# projeto_jcarlos_compacta_C_pia_em_confli.net
KiCad netlist of a schematic drawn in EAGLE
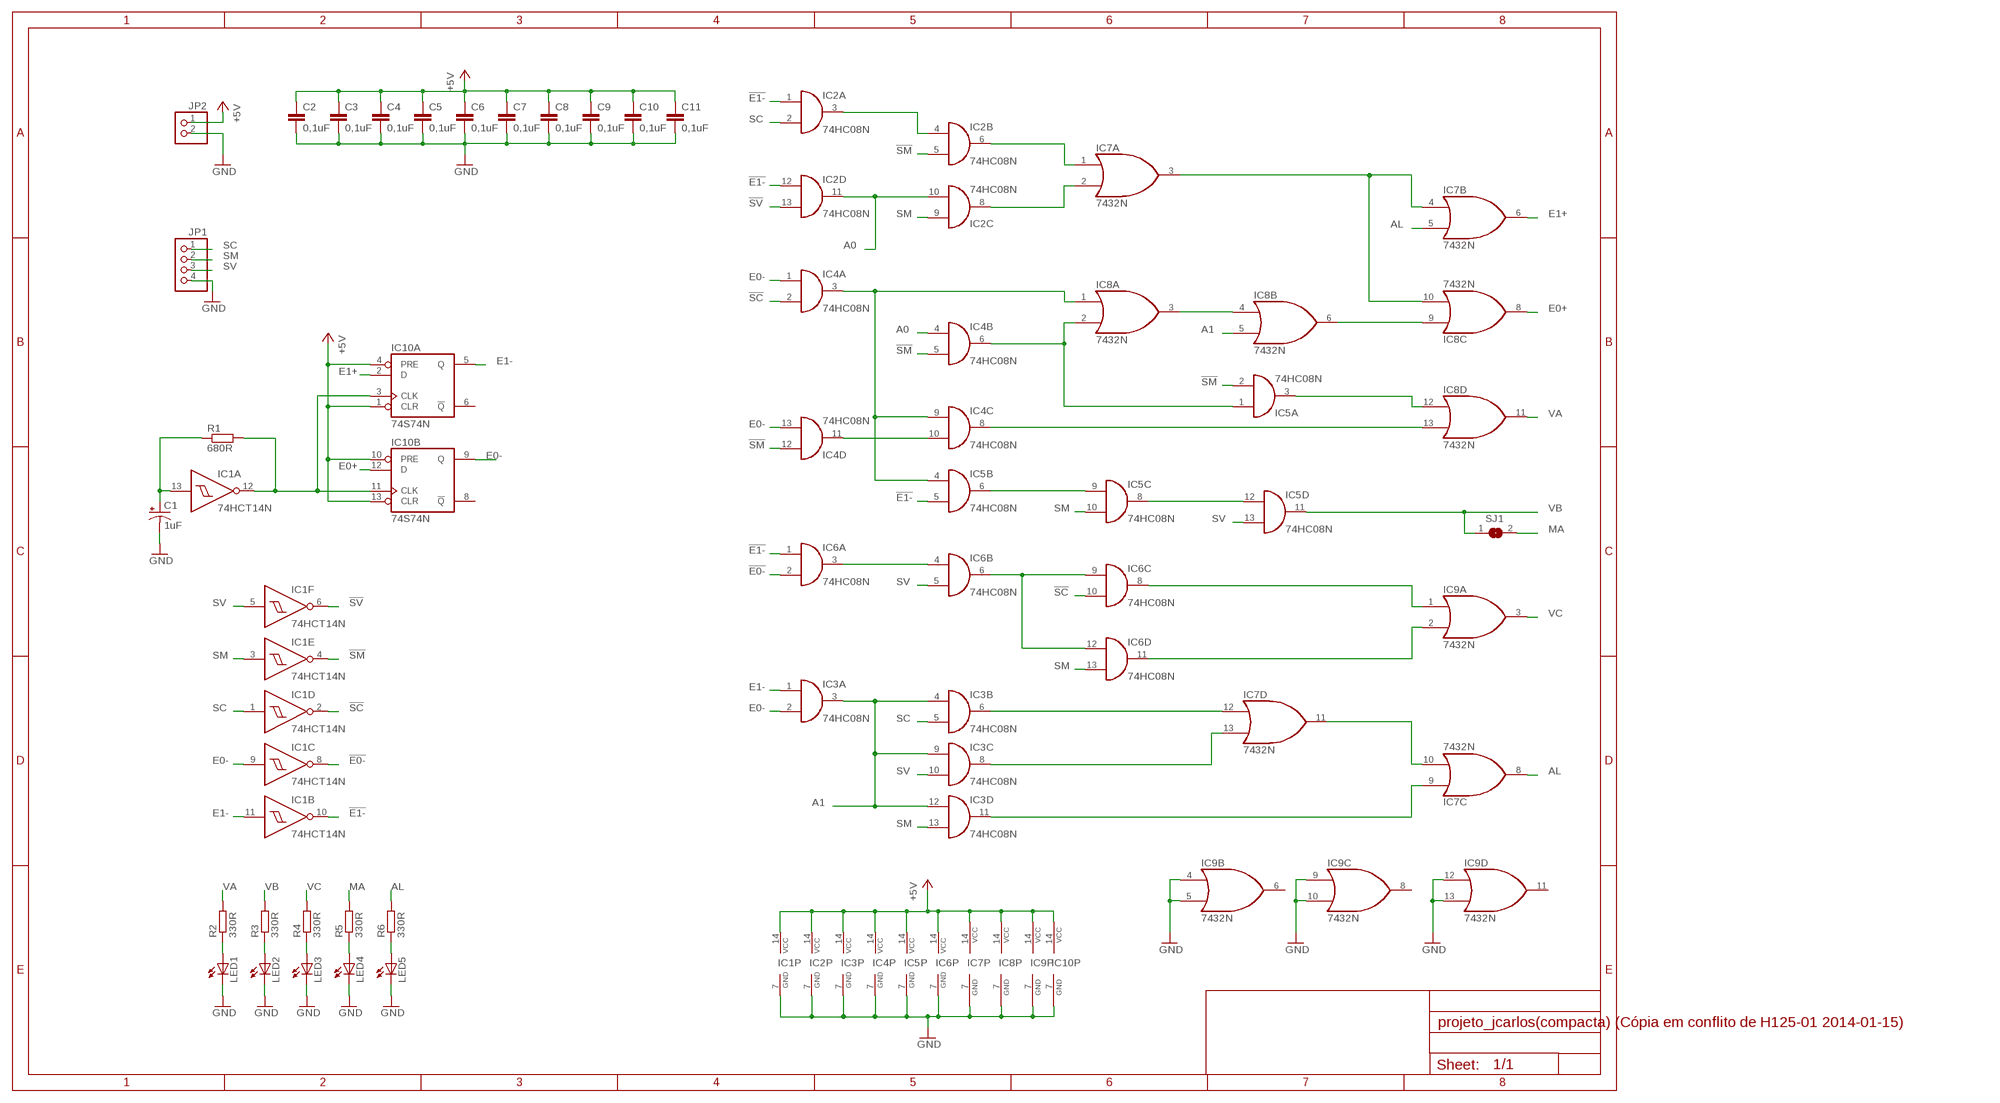
[diagram p0: schematic, sheet 1]

(export (version "E")
  (design (tool "Eeschema 10.0.6"))
  (components
    (comp (ref "C1")
      (value "1uF")
      (footprint "eagle-import:E5-6")
      (libsource (lib "eagle-import") (part "CPOL-USE5-6"))
    )
    (comp (ref "C2")
      (value "0,1uF")
      (footprint "eagle-import:C050-025X075")
      (libsource (lib "eagle-import") (part "C-EU050-025X075"))
    )
    (comp (ref "C3")
      (value "0,1uF")
      (footprint "eagle-import:C050-025X075")
      (libsource (lib "eagle-import") (part "C-EU050-025X075"))
    )
    (comp (ref "C4")
      (value "0,1uF")
      (footprint "eagle-import:C050-025X075")
      (libsource (lib "eagle-import") (part "C-EU050-025X075"))
    )
    (comp (ref "C5")
      (value "0,1uF")
      (footprint "eagle-import:C050-025X075")
      (libsource (lib "eagle-import") (part "C-EU050-025X075"))
    )
    (comp (ref "C6")
      (value "0,1uF")
      (footprint "eagle-import:C050-025X075")
      (libsource (lib "eagle-import") (part "C-EU050-025X075"))
    )
    (comp (ref "C7")
      (value "0,1uF")
      (footprint "eagle-import:C050-025X075")
      (libsource (lib "eagle-import") (part "C-EU050-025X075"))
    )
    (comp (ref "C8")
      (value "0,1uF")
      (footprint "eagle-import:C050-025X075")
      (libsource (lib "eagle-import") (part "C-EU050-025X075"))
    )
    (comp (ref "C9")
      (value "0,1uF")
      (footprint "eagle-import:C050-025X075")
      (libsource (lib "eagle-import") (part "C-EU050-025X075"))
    )
    (comp (ref "C10")
      (value "0,1uF")
      (footprint "eagle-import:C050-025X075")
      (libsource (lib "eagle-import") (part "C-EU050-025X075"))
    )
    (comp (ref "C11")
      (value "0,1uF")
      (footprint "eagle-import:C050-025X075")
      (libsource (lib "eagle-import") (part "C-EU050-025X075"))
    )
    (comp (ref "IC1")
      (value "74HCT14N")
      (footprint "eagle-import:DIL14")
      (libsource (lib "eagle-import") (part "7414NHCT"))
    )
    (comp (ref "IC2")
      (value "74HC08N")
      (footprint "eagle-import:DIL14")
      (libsource (lib "eagle-import") (part "7408NHC"))
    )
    (comp (ref "IC3")
      (value "74HC08N")
      (footprint "eagle-import:DIL14")
      (libsource (lib "eagle-import") (part "7408NHC"))
    )
    (comp (ref "IC4")
      (value "74HC08N")
      (footprint "eagle-import:DIL14")
      (libsource (lib "eagle-import") (part "7408NHC"))
    )
    (comp (ref "IC5")
      (value "74HC08N")
      (footprint "eagle-import:DIL14")
      (libsource (lib "eagle-import") (part "7408NHC"))
    )
    (comp (ref "IC6")
      (value "74HC08N")
      (footprint "eagle-import:DIL14")
      (libsource (lib "eagle-import") (part "7408NHC"))
    )
    (comp (ref "IC7")
      (value "7432N")
      (footprint "eagle-import:DIL14")
      (libsource (lib "eagle-import") (part "7432N"))
    )
    (comp (ref "IC8")
      (value "7432N")
      (footprint "eagle-import:DIL14")
      (libsource (lib "eagle-import") (part "7432N"))
    )
    (comp (ref "IC9")
      (value "7432N")
      (footprint "eagle-import:DIL14")
      (libsource (lib "eagle-import") (part "7432N"))
    )
    (comp (ref "IC10")
      (value "74S74N")
      (footprint "eagle-import:DIL14")
      (libsource (lib "eagle-import") (part "7474NS"))
    )
    (comp (ref "JP1")
      (value "PINHD-1X4")
      (footprint "eagle-import:1X04")
      (libsource (lib "eagle-import") (part "PINHD-1X4"))
    )
    (comp (ref "JP2")
      (value "PINHD-1X2")
      (footprint "eagle-import:1X02")
      (libsource (lib "eagle-import") (part "PINHD-1X2"))
    )
    (comp (ref "LED1")
      (value "LED5MM")
      (footprint "eagle-import:LED5MM")
      (libsource (lib "eagle-import") (part "LED5MM"))
    )
    (comp (ref "LED2")
      (value "LED5MM")
      (footprint "eagle-import:LED5MM")
      (libsource (lib "eagle-import") (part "LED5MM"))
    )
    (comp (ref "LED3")
      (value "LED5MM")
      (footprint "eagle-import:LED5MM")
      (libsource (lib "eagle-import") (part "LED5MM"))
    )
    (comp (ref "LED4")
      (value "LED5MM")
      (footprint "eagle-import:LED5MM")
      (libsource (lib "eagle-import") (part "LED5MM"))
    )
    (comp (ref "LED5")
      (value "LED5MM")
      (footprint "eagle-import:LED5MM")
      (libsource (lib "eagle-import") (part "LED5MM"))
    )
    (comp (ref "R1")
      (value "680R")
      (footprint "eagle-import:0204_5")
      (libsource (lib "eagle-import") (part "R-EU_0204/5"))
    )
    (comp (ref "R2")
      (value "330R")
      (footprint "eagle-import:0207_10")
      (libsource (lib "eagle-import") (part "R-EU_0207/10"))
    )
    (comp (ref "R3")
      (value "330R")
      (footprint "eagle-import:0207_10")
      (libsource (lib "eagle-import") (part "R-EU_0207/10"))
    )
    (comp (ref "R4")
      (value "330R")
      (footprint "eagle-import:0207_10")
      (libsource (lib "eagle-import") (part "R-EU_0207/10"))
    )
    (comp (ref "R5")
      (value "330R")
      (footprint "eagle-import:0207_10")
      (libsource (lib "eagle-import") (part "R-EU_0207/10"))
    )
    (comp (ref "R6")
      (value "330R")
      (footprint "eagle-import:0207_10")
      (libsource (lib "eagle-import") (part "R-EU_0207/10"))
    )
    (comp (ref "SJ1") (value "SJ") (footprint "eagle-import:SJ") (libsource (lib "eagle-import") (part "SJ")))
  )
  (nets
    (net (code "1") (name "+5V") (class "Default")
      (node (ref "C10") (pin "1") (pinfunction "1_1") (pintype "passive"))
      (node (ref "C11") (pin "1") (pinfunction "1_1") (pintype "passive"))
      (node (ref "C2") (pin "1") (pinfunction "1_1") (pintype "passive"))
      (node (ref "C3") (pin "1") (pinfunction "1_1") (pintype "passive"))
      (node (ref "C4") (pin "1") (pinfunction "1_1") (pintype "passive"))
      (node (ref "C5") (pin "1") (pinfunction "1_1") (pintype "passive"))
      (node (ref "C6") (pin "1") (pinfunction "1_1") (pintype "passive"))
      (node (ref "C7") (pin "1") (pinfunction "1_1") (pintype "passive"))
      (node (ref "C8") (pin "1") (pinfunction "1_1") (pintype "passive"))
      (node (ref "C9") (pin "1") (pinfunction "1_1") (pintype "passive"))
      (node (ref "IC1") (pin "14") (pinfunction "VCC_14") (pintype "power_in"))
      (node (ref "IC10") (pin "1") (pinfunction "CLR_1") (pintype "input"))
      (node (ref "IC10") (pin "10") (pinfunction "PRE_10") (pintype "input"))
      (node (ref "IC10") (pin "13") (pinfunction "CLR_13") (pintype "input"))
      (node (ref "IC10") (pin "14") (pinfunction "VCC_14") (pintype "power_in"))
      (node (ref "IC10") (pin "4") (pinfunction "PRE_4") (pintype "input"))
      (node (ref "IC2") (pin "14") (pinfunction "VCC_14") (pintype "power_in"))
      (node (ref "IC3") (pin "14") (pinfunction "VCC_14") (pintype "power_in"))
      (node (ref "IC4") (pin "14") (pinfunction "VCC_14") (pintype "power_in"))
      (node (ref "IC5") (pin "14") (pinfunction "VCC_14") (pintype "power_in"))
      (node (ref "IC6") (pin "14") (pinfunction "VCC_14") (pintype "power_in"))
      (node (ref "IC7") (pin "14") (pinfunction "VCC_14") (pintype "power_in"))
      (node (ref "IC8") (pin "14") (pinfunction "VCC_14") (pintype "power_in"))
      (node (ref "IC9") (pin "14") (pinfunction "VCC_14") (pintype "power_in"))
      (node (ref "JP2") (pin "1") (pinfunction "1_1") (pintype "passive"))
    )
    (net (code "2") (name "/A0") (class "Default")
      (node (ref "IC2") (pin "10") (pinfunction "I1_10") (pintype "input"))
      (node (ref "IC2") (pin "11") (pinfunction "O_11") (pintype "output"))
      (node (ref "IC4") (pin "4") (pinfunction "I0_4") (pintype "input"))
    )
    (net (code "3") (name "/A1") (class "Default")
      (node (ref "IC3") (pin "12") (pinfunction "I0_12") (pintype "input"))
      (node (ref "IC3") (pin "3") (pinfunction "O_3") (pintype "output"))
      (node (ref "IC3") (pin "4") (pinfunction "I0_4") (pintype "input"))
      (node (ref "IC3") (pin "9") (pinfunction "I0_9") (pintype "input"))
      (node (ref "IC8") (pin "5") (pinfunction "I1_5") (pintype "input"))
    )
    (net (code "4") (name "/AL") (class "Default")
      (node (ref "IC7") (pin "5") (pinfunction "I1_5") (pintype "input"))
      (node (ref "IC7") (pin "8") (pinfunction "O_8") (pintype "output"))
      (node (ref "R6") (pin "2") (pinfunction "2_2") (pintype "passive"))
    )
    (net (code "5") (name "/E0+") (class "Default")
      (node (ref "IC10") (pin "12") (pinfunction "D_12") (pintype "input"))
      (node (ref "IC8") (pin "8") (pinfunction "O_8") (pintype "output"))
    )
    (net (code "6") (name "/E0-") (class "Default")
      (node (ref "IC1") (pin "9") (pinfunction "I_9") (pintype "input"))
      (node (ref "IC10") (pin "9") (pinfunction "Q_9") (pintype "output"))
      (node (ref "IC3") (pin "2") (pinfunction "I1_2") (pintype "input"))
      (node (ref "IC4") (pin "1") (pinfunction "I0_1") (pintype "input"))
      (node (ref "IC4") (pin "13") (pinfunction "I1_13") (pintype "input"))
    )
    (net (code "7") (name "/E1+") (class "Default")
      (node (ref "IC10") (pin "2") (pinfunction "D_2") (pintype "input"))
      (node (ref "IC7") (pin "6") (pinfunction "O_6") (pintype "output"))
    )
    (net (code "8") (name "/E1-") (class "Default")
      (node (ref "IC1") (pin "11") (pinfunction "I_11") (pintype "input"))
      (node (ref "IC10") (pin "5") (pinfunction "Q_5") (pintype "output"))
      (node (ref "IC3") (pin "1") (pinfunction "I0_1") (pintype "input"))
    )
    (net (code "9") (name "/MA") (class "Default")
      (node (ref "R5") (pin "2") (pinfunction "2_2") (pintype "passive"))
      (node (ref "SJ1") (pin "2") (pinfunction "2_2") (pintype "passive"))
    )
    (net (code "10") (name "/SC") (class "Default")
      (node (ref "IC1") (pin "1") (pinfunction "I_1") (pintype "input"))
      (node (ref "IC2") (pin "2") (pinfunction "I1_2") (pintype "input"))
      (node (ref "IC3") (pin "5") (pinfunction "I1_5") (pintype "input"))
      (node (ref "JP1") (pin "1") (pinfunction "1_1") (pintype "passive"))
    )
    (net (code "11") (name "/SM") (class "Default")
      (node (ref "IC1") (pin "3") (pinfunction "I_3") (pintype "input"))
      (node (ref "IC2") (pin "9") (pinfunction "I0_9") (pintype "input"))
      (node (ref "IC3") (pin "13") (pinfunction "I1_13") (pintype "input"))
      (node (ref "IC5") (pin "10") (pinfunction "I1_10") (pintype "input"))
      (node (ref "IC6") (pin "13") (pinfunction "I1_13") (pintype "input"))
      (node (ref "JP1") (pin "2") (pinfunction "2_2") (pintype "passive"))
    )
    (net (code "12") (name "/SV") (class "Default")
      (node (ref "IC1") (pin "5") (pinfunction "I_5") (pintype "input"))
      (node (ref "IC3") (pin "10") (pinfunction "I1_10") (pintype "input"))
      (node (ref "IC5") (pin "13") (pinfunction "I1_13") (pintype "input"))
      (node (ref "IC6") (pin "5") (pinfunction "I1_5") (pintype "input"))
      (node (ref "JP1") (pin "3") (pinfunction "3_3") (pintype "passive"))
    )
    (net (code "13") (name "/VA") (class "Default")
      (node (ref "IC8") (pin "11") (pinfunction "O_11") (pintype "output"))
      (node (ref "R2") (pin "2") (pinfunction "2_2") (pintype "passive"))
    )
    (net (code "14") (name "/VB") (class "Default")
      (node (ref "IC5") (pin "11") (pinfunction "O_11") (pintype "output"))
      (node (ref "R3") (pin "2") (pinfunction "2_2") (pintype "passive"))
      (node (ref "SJ1") (pin "1") (pinfunction "1_1") (pintype "passive"))
    )
    (net (code "15") (name "/VC") (class "Default")
      (node (ref "IC9") (pin "3") (pinfunction "O_3") (pintype "output"))
      (node (ref "R4") (pin "2") (pinfunction "2_2") (pintype "passive"))
    )
    (net (code "16") (name "/~{E0-}") (class "Default")
      (node (ref "IC1") (pin "8") (pinfunction "O_8") (pintype "output"))
      (node (ref "IC6") (pin "2") (pinfunction "I1_2") (pintype "input"))
    )
    (net (code "17") (name "/~{E1-}") (class "Default")
      (node (ref "IC1") (pin "10") (pinfunction "O_10") (pintype "output"))
      (node (ref "IC2") (pin "1") (pinfunction "I0_1") (pintype "input"))
      (node (ref "IC2") (pin "12") (pinfunction "I0_12") (pintype "input"))
      (node (ref "IC5") (pin "5") (pinfunction "I1_5") (pintype "input"))
      (node (ref "IC6") (pin "1") (pinfunction "I0_1") (pintype "input"))
    )
    (net (code "18") (name "/~{SC}") (class "Default")
      (node (ref "IC1") (pin "2") (pinfunction "O_2") (pintype "output"))
      (node (ref "IC4") (pin "2") (pinfunction "I1_2") (pintype "input"))
      (node (ref "IC6") (pin "10") (pinfunction "I1_10") (pintype "input"))
    )
    (net (code "19") (name "/~{SM}") (class "Default")
      (node (ref "IC1") (pin "4") (pinfunction "O_4") (pintype "output"))
      (node (ref "IC2") (pin "5") (pinfunction "I1_5") (pintype "input"))
      (node (ref "IC4") (pin "12") (pinfunction "I0_12") (pintype "input"))
      (node (ref "IC4") (pin "5") (pinfunction "I1_5") (pintype "input"))
      (node (ref "IC5") (pin "2") (pinfunction "I1_2") (pintype "input"))
    )
    (net (code "20") (name "/~{SV}") (class "Default")
      (node (ref "IC1") (pin "6") (pinfunction "O_6") (pintype "output"))
      (node (ref "IC2") (pin "13") (pinfunction "I1_13") (pintype "input"))
    )
    (net (code "21") (name "GND") (class "Default")
      (node (ref "C1") (pin "-") (pinfunction "-_-") (pintype "passive"))
      (node (ref "C10") (pin "2") (pinfunction "2_2") (pintype "passive"))
      (node (ref "C11") (pin "2") (pinfunction "2_2") (pintype "passive"))
      (node (ref "C2") (pin "2") (pinfunction "2_2") (pintype "passive"))
      (node (ref "C3") (pin "2") (pinfunction "2_2") (pintype "passive"))
      (node (ref "C4") (pin "2") (pinfunction "2_2") (pintype "passive"))
      (node (ref "C5") (pin "2") (pinfunction "2_2") (pintype "passive"))
      (node (ref "C6") (pin "2") (pinfunction "2_2") (pintype "passive"))
      (node (ref "C7") (pin "2") (pinfunction "2_2") (pintype "passive"))
      (node (ref "C8") (pin "2") (pinfunction "2_2") (pintype "passive"))
      (node (ref "C9") (pin "2") (pinfunction "2_2") (pintype "passive"))
      (node (ref "IC1") (pin "7") (pinfunction "GND_7") (pintype "power_in"))
      (node (ref "IC10") (pin "7") (pinfunction "GND_7") (pintype "power_in"))
      (node (ref "IC2") (pin "7") (pinfunction "GND_7") (pintype "power_in"))
      (node (ref "IC3") (pin "7") (pinfunction "GND_7") (pintype "power_in"))
      (node (ref "IC4") (pin "7") (pinfunction "GND_7") (pintype "power_in"))
      (node (ref "IC5") (pin "7") (pinfunction "GND_7") (pintype "power_in"))
      (node (ref "IC6") (pin "7") (pinfunction "GND_7") (pintype "power_in"))
      (node (ref "IC7") (pin "7") (pinfunction "GND_7") (pintype "power_in"))
      (node (ref "IC8") (pin "7") (pinfunction "GND_7") (pintype "power_in"))
      (node (ref "IC9") (pin "10") (pinfunction "I1_10") (pintype "input"))
      (node (ref "IC9") (pin "12") (pinfunction "I0_12") (pintype "input"))
      (node (ref "IC9") (pin "13") (pinfunction "I1_13") (pintype "input"))
      (node (ref "IC9") (pin "4") (pinfunction "I0_4") (pintype "input"))
      (node (ref "IC9") (pin "5") (pinfunction "I1_5") (pintype "input"))
      (node (ref "IC9") (pin "7") (pinfunction "GND_7") (pintype "power_in"))
      (node (ref "IC9") (pin "9") (pinfunction "I0_9") (pintype "input"))
      (node (ref "JP1") (pin "4") (pinfunction "4_4") (pintype "passive"))
      (node (ref "JP2") (pin "2") (pinfunction "2_2") (pintype "passive"))
      (node (ref "LED1") (pin "K") (pinfunction "C_K") (pintype "passive"))
      (node (ref "LED2") (pin "K") (pinfunction "C_K") (pintype "passive"))
      (node (ref "LED3") (pin "K") (pinfunction "C_K") (pintype "passive"))
      (node (ref "LED4") (pin "K") (pinfunction "C_K") (pintype "passive"))
      (node (ref "LED5") (pin "K") (pinfunction "C_K") (pintype "passive"))
    )
    (net (code "22") (name "Net-(IC1A-I)") (class "Default")
      (node (ref "C1") (pin "+") (pinfunction "+_+") (pintype "passive"))
      (node (ref "IC1") (pin "13") (pinfunction "I_13") (pintype "input"))
      (node (ref "R1") (pin "1") (pinfunction "1_1") (pintype "passive"))
    )
    (net (code "23") (name "Net-(IC2A-O)") (class "Default")
      (node (ref "IC2") (pin "3") (pinfunction "O_3") (pintype "output"))
      (node (ref "IC2") (pin "4") (pinfunction "I0_4") (pintype "input"))
    )
    (net (code "24") (name "Net-(IC2B-O)") (class "Default")
      (node (ref "IC2") (pin "6") (pinfunction "O_6") (pintype "output"))
      (node (ref "IC7") (pin "1") (pinfunction "I0_1") (pintype "input"))
    )
    (net (code "25") (name "Net-(IC2C-O)") (class "Default")
      (node (ref "IC2") (pin "8") (pinfunction "O_8") (pintype "output"))
      (node (ref "IC7") (pin "2") (pinfunction "I1_2") (pintype "input"))
    )
    (net (code "26") (name "Net-(IC3B-O)") (class "Default")
      (node (ref "IC3") (pin "6") (pinfunction "O_6") (pintype "output"))
      (node (ref "IC7") (pin "12") (pinfunction "I0_12") (pintype "input"))
    )
    (net (code "27") (name "Net-(IC3C-O)") (class "Default")
      (node (ref "IC3") (pin "8") (pinfunction "O_8") (pintype "output"))
      (node (ref "IC7") (pin "13") (pinfunction "I1_13") (pintype "input"))
    )
    (net (code "28") (name "Net-(IC3D-O)") (class "Default")
      (node (ref "IC3") (pin "11") (pinfunction "O_11") (pintype "output"))
      (node (ref "IC7") (pin "9") (pinfunction "I0_9") (pintype "input"))
    )
    (net (code "29") (name "Net-(IC4A-O)") (class "Default")
      (node (ref "IC4") (pin "3") (pinfunction "O_3") (pintype "output"))
      (node (ref "IC4") (pin "9") (pinfunction "I0_9") (pintype "input"))
      (node (ref "IC5") (pin "4") (pinfunction "I0_4") (pintype "input"))
      (node (ref "IC8") (pin "1") (pinfunction "I0_1") (pintype "input"))
    )
    (net (code "30") (name "Net-(IC4B-O)") (class "Default")
      (node (ref "IC4") (pin "6") (pinfunction "O_6") (pintype "output"))
      (node (ref "IC5") (pin "1") (pinfunction "I0_1") (pintype "input"))
      (node (ref "IC8") (pin "2") (pinfunction "I1_2") (pintype "input"))
    )
    (net (code "31") (name "Net-(IC4C-I1)") (class "Default")
      (node (ref "IC4") (pin "10") (pinfunction "I1_10") (pintype "input"))
      (node (ref "IC4") (pin "11") (pinfunction "O_11") (pintype "output"))
    )
    (net (code "32") (name "Net-(IC4C-O)") (class "Default")
      (node (ref "IC4") (pin "8") (pinfunction "O_8") (pintype "output"))
      (node (ref "IC8") (pin "13") (pinfunction "I1_13") (pintype "input"))
    )
    (net (code "33") (name "Net-(IC5A-O)") (class "Default")
      (node (ref "IC5") (pin "3") (pinfunction "O_3") (pintype "output"))
      (node (ref "IC8") (pin "12") (pinfunction "I0_12") (pintype "input"))
    )
    (net (code "34") (name "Net-(IC5B-O)") (class "Default")
      (node (ref "IC5") (pin "6") (pinfunction "O_6") (pintype "output"))
      (node (ref "IC5") (pin "9") (pinfunction "I0_9") (pintype "input"))
    )
    (net (code "35") (name "Net-(IC5C-O)") (class "Default")
      (node (ref "IC5") (pin "12") (pinfunction "I0_12") (pintype "input"))
      (node (ref "IC5") (pin "8") (pinfunction "O_8") (pintype "output"))
    )
    (net (code "36") (name "Net-(IC6A-O)") (class "Default")
      (node (ref "IC6") (pin "3") (pinfunction "O_3") (pintype "output"))
      (node (ref "IC6") (pin "4") (pinfunction "I0_4") (pintype "input"))
    )
    (net (code "37") (name "Net-(IC6B-O)") (class "Default")
      (node (ref "IC6") (pin "12") (pinfunction "I0_12") (pintype "input"))
      (node (ref "IC6") (pin "6") (pinfunction "O_6") (pintype "output"))
      (node (ref "IC6") (pin "9") (pinfunction "I0_9") (pintype "input"))
    )
    (net (code "38") (name "Net-(IC6C-O)") (class "Default")
      (node (ref "IC6") (pin "8") (pinfunction "O_8") (pintype "output"))
      (node (ref "IC9") (pin "1") (pinfunction "I0_1") (pintype "input"))
    )
    (net (code "39") (name "Net-(IC6D-O)") (class "Default")
      (node (ref "IC6") (pin "11") (pinfunction "O_11") (pintype "output"))
      (node (ref "IC9") (pin "2") (pinfunction "I1_2") (pintype "input"))
    )
    (net (code "40") (name "Net-(IC7A-O)") (class "Default")
      (node (ref "IC7") (pin "3") (pinfunction "O_3") (pintype "output"))
      (node (ref "IC7") (pin "4") (pinfunction "I0_4") (pintype "input"))
      (node (ref "IC8") (pin "10") (pinfunction "I1_10") (pintype "input"))
    )
    (net (code "41") (name "Net-(IC7C-I1)") (class "Default")
      (node (ref "IC7") (pin "10") (pinfunction "I1_10") (pintype "input"))
      (node (ref "IC7") (pin "11") (pinfunction "O_11") (pintype "output"))
    )
    (net (code "42") (name "Net-(IC8A-O)") (class "Default")
      (node (ref "IC8") (pin "3") (pinfunction "O_3") (pintype "output"))
      (node (ref "IC8") (pin "4") (pinfunction "I0_4") (pintype "input"))
    )
    (net (code "43") (name "Net-(IC8B-O)") (class "Default")
      (node (ref "IC8") (pin "6") (pinfunction "O_6") (pintype "output"))
      (node (ref "IC8") (pin "9") (pinfunction "I0_9") (pintype "input"))
    )
    (net (code "44") (name "Net-(IC10A-CLK)") (class "Default")
      (node (ref "IC1") (pin "12") (pinfunction "O_12") (pintype "output"))
      (node (ref "IC10") (pin "11") (pinfunction "CLK_11") (pintype "input"))
      (node (ref "IC10") (pin "3") (pinfunction "CLK_3") (pintype "input"))
      (node (ref "R1") (pin "2") (pinfunction "2_2") (pintype "passive"))
    )
    (net (code "45") (name "Net-(LED1-PadA)") (class "Default")
      (node (ref "LED1") (pin "A") (pinfunction "A_A") (pintype "passive"))
      (node (ref "R2") (pin "1") (pinfunction "1_1") (pintype "passive"))
    )
    (net (code "46") (name "Net-(LED2-PadA)") (class "Default")
      (node (ref "LED2") (pin "A") (pinfunction "A_A") (pintype "passive"))
      (node (ref "R3") (pin "1") (pinfunction "1_1") (pintype "passive"))
    )
    (net (code "47") (name "Net-(LED3-PadA)") (class "Default")
      (node (ref "LED3") (pin "A") (pinfunction "A_A") (pintype "passive"))
      (node (ref "R4") (pin "1") (pinfunction "1_1") (pintype "passive"))
    )
    (net (code "48") (name "Net-(LED4-PadA)") (class "Default")
      (node (ref "LED4") (pin "A") (pinfunction "A_A") (pintype "passive"))
      (node (ref "R5") (pin "1") (pinfunction "1_1") (pintype "passive"))
    )
    (net (code "49") (name "Net-(LED5-PadA)") (class "Default")
      (node (ref "LED5") (pin "A") (pinfunction "A_A") (pintype "passive"))
      (node (ref "R6") (pin "1") (pinfunction "1_1") (pintype "passive"))
    )
    (net (code "50") (name "unconnected-(IC9B-O-Pad6)") (class "Default")
      (node (ref "IC9") (pin "6") (pinfunction "O_6") (pintype "output"))
    )
    (net (code "51") (name "unconnected-(IC9C-O-Pad8)") (class "Default")
      (node (ref "IC9") (pin "8") (pinfunction "O_8") (pintype "output"))
    )
    (net (code "52") (name "unconnected-(IC9D-O-Pad11)") (class "Default")
      (node (ref "IC9") (pin "11") (pinfunction "O_11") (pintype "output"))
    )
    (net (code "53") (name "unconnected-(IC10A-~{Q}-Pad6)") (class "Default")
      (node (ref "IC10") (pin "6") (pinfunction "~{Q}_6") (pintype "output"))
    )
    (net (code "54") (name "unconnected-(IC10B-~{Q}-Pad8)") (class "Default")
      (node (ref "IC10") (pin "8") (pinfunction "~{Q}_8") (pintype "output"))
    )
  )
)
